# controleRemoto.net
KiCad netlist of a schematic drawn in Altium Designer
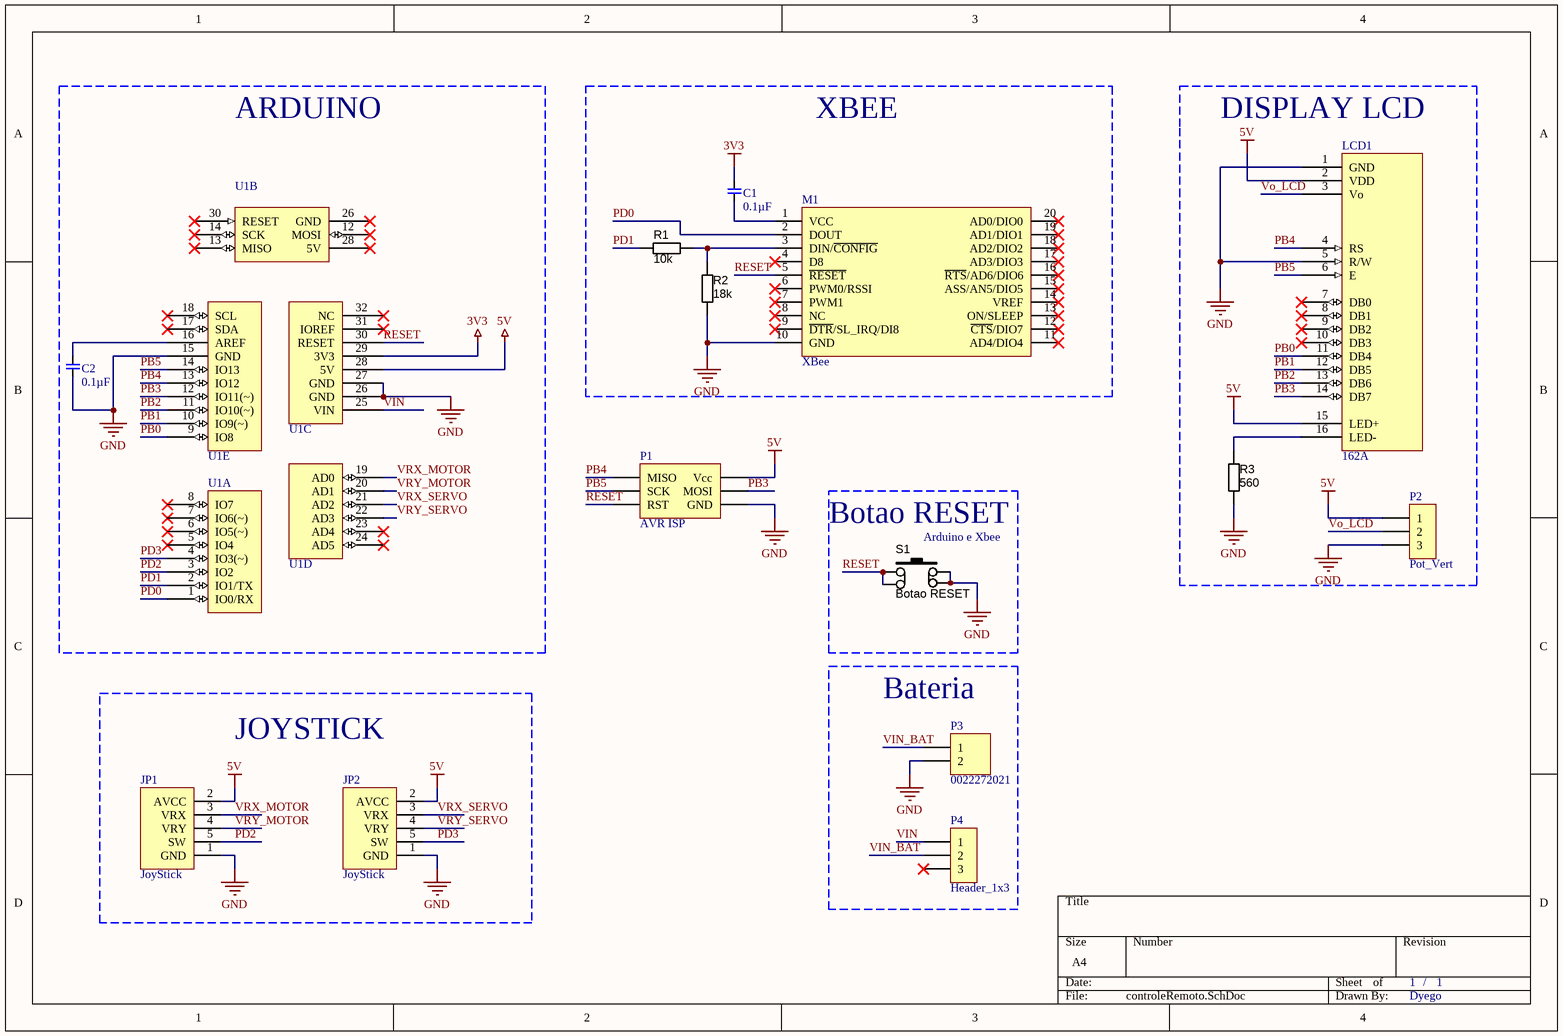
[diagram p0: controleRemoto.SchDoc]

(export (version "E")
  (design (tool "Eeschema 10.0.6"))
  (components
    (comp (ref "C1")
      (value "0.1µF")
      (footprint "C100-200-100")
      (description "Non-polarised capacitor")
      (fields
        (field (name "MANUFACTURER PART NUMBER") "C320C104K1R5TA7301")
        (field (name "TOLERANCE") "±10%")
      )
      (libsource (lib "DatabaseAltium") (part "Capacitor_non_polarized"))
    )
    (comp (ref "C2")
      (value "0.1µF")
      (footprint "C100-200-100")
      (description "Non-polarised capacitor")
      (fields
        (field (name "MANUFACTURER PART NUMBER") "C320C104K1R5TA7301")
        (field (name "TOLERANCE") "±10%")
      )
      (libsource (lib "DatabaseAltium") (part "Capacitor_non_polarized"))
    )
    (comp (ref "JP1")
      (value "JoyStick")
      (footprint "Modulo Joystick Dual Eixo XY")
      (libsource (lib "DatabaseAltium") (part "Joystick"))
    )
    (comp (ref "JP2")
      (value "JoyStick")
      (footprint "Modulo Joystick Dual Eixo XY")
      (libsource (lib "DatabaseAltium") (part "Joystick"))
    )
    (comp (ref "LCD1")
      (value "162A")
      (footprint "DISPLAY 16x2")
      (description "16 char * 2 line LCD character display with b/light")
      (fields (field (name "MANUFACTURERPARTNUMBER") "LCM-S01602DTR/A"))
      (libsource (lib "DatabaseAltium") (part "162A"))
    )
    (comp (ref "M1")
      (value "XBee")
      (footprint "XBee")
      (description "XBee RF Multipoint Module")
      (fields (field (name "MANUFACTURERPARTNUMBER") "XB24CZ7WIT-004"))
      (libsource (lib "DatabaseAltium") (part "XBee"))
    )
    (comp (ref "P1")
      (value "AVR ISP")
      (footprint "HDR-M-2x3-2.54mm-180-9.2mm")
      (description "ARV ISP Connector")
      (fields (field (name "MANUFACTURERPARTNUMBER") "AVR_ISP"))
      (libsource (lib "DatabaseAltium") (part "AVR_ISP"))
    )
    (comp (ref "P2")
      (value "Pot_Vert")
      (footprint "Pot_Vert")
      (description "Header, 1 Line, 3 Columns, 3 Pins")
      (libsource (lib "DatabaseAltium") (part "Pot_Vert"))
    )
    (comp (ref "P3")
      (value "0022272021")
      (footprint "KK_2")
      (libsource (lib "DatabaseAltium") (part "CONN_2"))
    )
    (comp (ref "P4")
      (value "Header_1x3")
      (footprint "Chave Alavanca MTS103")
      (description "Header, 1 Line, 3 Columns, 3 Pins")
      (fields (field (name "MANUFACTURERPARTNUMBER") "Chave alavanca"))
      (libsource (lib "DatabaseAltium") (part "Header_1x3"))
    )
    (comp (ref "R1")
      (value "10k")
      (footprint "RESTH_AXIAL-0.4")
      (description "Resistor")
      (fields (field (name "MANUFACTURER PART NUMBER") "CF18JT10K0") (field (name "TOLERANCE") "±5%"))
      (libsource (lib "DatabaseAltium") (part "Resistor"))
    )
    (comp (ref "R2")
      (value "18k")
      (footprint "RESTH_AXIAL-0.4")
      (description "Resistor")
      (fields (field (name "MANUFACTURER PART NUMBER") "CF18JT18K0") (field (name "TOLERANCE") "±5%"))
      (libsource (lib "") (part "Resistor_1"))
    )
    (comp (ref "R3")
      (value "560")
      (footprint "RESTH_AXIAL-0.4")
      (description "Resistor")
      (fields (field (name "MANUFACTURER PART NUMBER") "CF18JT560R") (field (name "TOLERANCE") "±5%"))
      (libsource (lib "") (part "Resistor_1"))
    )
    (comp (ref "S1")
      (value "Botao RESET")
      (footprint "DTS-6.0mm-6.0mm-THT")
      (fields (field (name "MANUFACTURERPARTNUMBER") "ADTS648NV"))
      (libsource (lib "DatabaseAltium") (part "PushButton"))
    )
    (comp (ref "U1")
      (value "Shield Arduino Uno Rv3 1")
      (footprint "Shield Arduino Uno Rv3 1")
      (libsource (lib "DatabaseAltium") (part "Arduino UNO Rev3"))
    )
  )
  (nets
    (net (code "1") (name "/PB0") (class "Default")
      (node (ref "LCD1") (pin "11") (pinfunction "DB4_11") (pintype "bidirectional"))
      (node (ref "U1") (pin "9") (pinfunction "IO8_9") (pintype "bidirectional"))
    )
    (net (code "2") (name "/PB1") (class "Default")
      (node (ref "LCD1") (pin "12") (pinfunction "DB5_12") (pintype "bidirectional"))
      (node (ref "U1") (pin "10") (pinfunction "IO9(~)_10") (pintype "bidirectional"))
    )
    (net (code "3") (name "/PB2") (class "Default")
      (node (ref "LCD1") (pin "13") (pinfunction "DB6_13") (pintype "bidirectional"))
      (node (ref "U1") (pin "11") (pinfunction "IO10(~)_11") (pintype "bidirectional"))
    )
    (net (code "4") (name "/PB3") (class "Default")
      (node (ref "LCD1") (pin "14") (pinfunction "DB7_14") (pintype "bidirectional"))
      (node (ref "P1") (pin "4") (pinfunction "MOSI_4") (pintype "passive"))
      (node (ref "U1") (pin "12") (pinfunction "IO11(~)_12") (pintype "bidirectional"))
    )
    (net (code "5") (name "/PB4") (class "Default")
      (node (ref "LCD1") (pin "4") (pinfunction "RS_4") (pintype "input"))
      (node (ref "P1") (pin "1") (pinfunction "MISO_1") (pintype "passive"))
      (node (ref "U1") (pin "13") (pinfunction "IO12_13") (pintype "bidirectional"))
    )
    (net (code "6") (name "/PB5") (class "Default")
      (node (ref "LCD1") (pin "6") (pinfunction "E_6") (pintype "input"))
      (node (ref "P1") (pin "3") (pinfunction "SCK_3") (pintype "passive"))
      (node (ref "U1") (pin "14") (pinfunction "IO13_14") (pintype "bidirectional"))
    )
    (net (code "7") (name "/PD0") (class "Default")
      (node (ref "M1") (pin "2") (pinfunction "DOUT_2") (pintype "passive"))
      (node (ref "U1") (pin "1") (pinfunction "IO0/RX_1") (pintype "bidirectional"))
    )
    (net (code "8") (name "/PD1") (class "Default")
      (node (ref "R1") (pin "1") (pinfunction "1_1") (pintype "passive"))
      (node (ref "U1") (pin "2") (pinfunction "IO1/TX_2") (pintype "bidirectional"))
    )
    (net (code "9") (name "/PD2") (class "Default")
      (node (ref "JP1") (pin "5") (pinfunction "SW_5") (pintype "passive"))
      (node (ref "U1") (pin "3") (pinfunction "IO2_3") (pintype "bidirectional"))
    )
    (net (code "10") (name "/PD3") (class "Default")
      (node (ref "JP2") (pin "5") (pinfunction "SW_5") (pintype "passive"))
      (node (ref "U1") (pin "4") (pinfunction "IO3(~)_4") (pintype "bidirectional"))
    )
    (net (code "11") (name "/RESET") (class "Default")
      (node (ref "M1") (pin "5") (pinfunction "~{RESET}_5") (pintype "passive"))
      (node (ref "P1") (pin "5") (pinfunction "RST_5") (pintype "passive"))
      (node (ref "S1") (pin "1") (pintype "passive"))
      (node (ref "U1") (pin "30") (pinfunction "RESET_30") (pintype "passive"))
    )
    (net (code "12") (name "/VIN") (class "Default")
      (node (ref "P4") (pin "1") (pinfunction "1_1") (pintype "passive"))
      (node (ref "U1") (pin "25") (pinfunction "VIN_25") (pintype "power_in"))
    )
    (net (code "13") (name "/VIN_BAT") (class "Default")
      (node (ref "P3") (pin "1") (pinfunction "1_1") (pintype "passive"))
      (node (ref "P4") (pin "2") (pinfunction "2_2") (pintype "passive"))
    )
    (net (code "14") (name "/VRX_MOTOR") (class "Default")
      (node (ref "JP1") (pin "3") (pinfunction "VRX_3") (pintype "passive"))
      (node (ref "U1") (pin "19") (pinfunction "AD0_19") (pintype "bidirectional"))
    )
    (net (code "15") (name "/VRX_SERVO") (class "Default")
      (node (ref "JP2") (pin "3") (pinfunction "VRX_3") (pintype "passive"))
      (node (ref "U1") (pin "21") (pinfunction "AD2_21") (pintype "bidirectional"))
    )
    (net (code "16") (name "/VRY_MOTOR") (class "Default")
      (node (ref "JP1") (pin "4") (pinfunction "VRY_4") (pintype "passive"))
      (node (ref "U1") (pin "20") (pinfunction "AD1_20") (pintype "bidirectional"))
    )
    (net (code "17") (name "/VRY_SERVO") (class "Default")
      (node (ref "JP2") (pin "4") (pinfunction "VRY_4") (pintype "passive"))
      (node (ref "U1") (pin "22") (pinfunction "AD3_22") (pintype "bidirectional"))
    )
    (net (code "18") (name "/Vo_LCD") (class "Default")
      (node (ref "LCD1") (pin "3") (pinfunction "Vo_3") (pintype "tri_state"))
      (node (ref "P2") (pin "2") (pinfunction "2_2") (pintype "passive"))
    )
    (net (code "19") (name "3V3") (class "Default")
      (node (ref "C1") (pin "2") (pinfunction "2_2") (pintype "passive"))
      (node (ref "U1") (pin "29") (pinfunction "3V3_29") (pintype "power_in"))
    )
    (net (code "20") (name "5V") (class "Default")
      (node (ref "JP1") (pin "2") (pinfunction "AVCC_2") (pintype "passive"))
      (node (ref "JP2") (pin "2") (pinfunction "AVCC_2") (pintype "passive"))
      (node (ref "LCD1") (pin "15") (pinfunction "LED+_15") (pintype "power_in"))
      (node (ref "LCD1") (pin "2") (pinfunction "VDD_2") (pintype "power_in"))
      (node (ref "P1") (pin "2") (pinfunction "Vcc_2") (pintype "passive"))
      (node (ref "P2") (pin "1") (pinfunction "1_1") (pintype "passive"))
      (node (ref "U1") (pin "28") (pinfunction "5V_28") (pintype "power_in"))
    )
    (net (code "21") (name "GND") (class "Default")
      (node (ref "C2") (pin "1") (pinfunction "1_1") (pintype "passive"))
      (node (ref "JP1") (pin "1") (pinfunction "GND_1") (pintype "passive"))
      (node (ref "JP2") (pin "1") (pinfunction "GND_1") (pintype "passive"))
      (node (ref "LCD1") (pin "1") (pinfunction "GND_1") (pintype "power_in"))
      (node (ref "LCD1") (pin "5") (pinfunction "R/W_5") (pintype "input"))
      (node (ref "M1") (pin "10") (pinfunction "GND_10") (pintype "passive"))
      (node (ref "P1") (pin "6") (pinfunction "GND_6") (pintype "passive"))
      (node (ref "P2") (pin "3") (pinfunction "3_3") (pintype "passive"))
      (node (ref "P3") (pin "2") (pinfunction "2_2") (pintype "passive"))
      (node (ref "R2") (pin "2") (pinfunction "2_2") (pintype "passive"))
      (node (ref "R3") (pin "2") (pinfunction "2_2") (pintype "passive"))
      (node (ref "S1") (pin "2") (pintype "passive"))
      (node (ref "U1") (pin "15") (pinfunction "GND_15") (pintype "power_in"))
      (node (ref "U1") (pin "26") (pinfunction "GND_26") (pintype "power_in"))
      (node (ref "U1") (pin "27") (pinfunction "GND_27") (pintype "power_in"))
    )
    (net (code "22") (name "Net-(LCD1-LED-)") (class "Default")
      (node (ref "LCD1") (pin "16") (pinfunction "LED-_16") (pintype "power_in"))
      (node (ref "R3") (pin "1") (pinfunction "1_1") (pintype "passive"))
    )
    (net (code "23") (name "Net-(M1-DIN{slash}~{CONFIG})") (class "Default")
      (node (ref "M1") (pin "3") (pinfunction "DIN/~{CONFIG}_3") (pintype "passive"))
      (node (ref "R1") (pin "2") (pinfunction "2_2") (pintype "passive"))
      (node (ref "R2") (pin "1") (pinfunction "1_1") (pintype "passive"))
    )
    (net (code "24") (name "Net-(M1-VCC)") (class "Default")
      (node (ref "C1") (pin "1") (pinfunction "1_1") (pintype "passive"))
      (node (ref "M1") (pin "1") (pinfunction "VCC_1") (pintype "passive"))
    )
    (net (code "25") (name "Net-(U1E-AREF)") (class "Default")
      (node (ref "C2") (pin "2") (pinfunction "2_2") (pintype "passive"))
      (node (ref "U1") (pin "16") (pinfunction "AREF_16") (pintype "passive"))
    )
    (net (code "26") (name "unconnected-(LCD1-DB0-Pad7)") (class "Default")
      (node (ref "LCD1") (pin "7") (pinfunction "DB0_7") (pintype "bidirectional+no_connect"))
    )
    (net (code "27") (name "unconnected-(LCD1-DB1-Pad8)") (class "Default")
      (node (ref "LCD1") (pin "8") (pinfunction "DB1_8") (pintype "bidirectional+no_connect"))
    )
    (net (code "28") (name "unconnected-(LCD1-DB2-Pad9)") (class "Default")
      (node (ref "LCD1") (pin "9") (pinfunction "DB2_9") (pintype "bidirectional+no_connect"))
    )
    (net (code "29") (name "unconnected-(LCD1-DB3-Pad10)") (class "Default")
      (node (ref "LCD1") (pin "10") (pinfunction "DB3_10") (pintype "bidirectional+no_connect"))
    )
    (net (code "30") (name "unconnected-(M1-AD0{slash}DIO0-Pad20)") (class "Default")
      (node (ref "M1") (pin "20") (pinfunction "AD0/DIO0_20") (pintype "passive+no_connect"))
    )
    (net (code "31") (name "unconnected-(M1-AD1{slash}DIO1-Pad19)") (class "Default")
      (node (ref "M1") (pin "19") (pinfunction "AD1/DIO1_19") (pintype "passive+no_connect"))
    )
    (net (code "32") (name "unconnected-(M1-AD2{slash}DIO2-Pad18)") (class "Default")
      (node (ref "M1") (pin "18") (pinfunction "AD2/DIO2_18") (pintype "passive+no_connect"))
    )
    (net (code "33") (name "unconnected-(M1-AD3{slash}DIO3-Pad17)") (class "Default")
      (node (ref "M1") (pin "17") (pinfunction "AD3/DIO3_17") (pintype "passive+no_connect"))
    )
    (net (code "34") (name "unconnected-(M1-AD4{slash}DIO4-Pad11)") (class "Default")
      (node (ref "M1") (pin "11") (pinfunction "AD4/DIO4_11") (pintype "passive+no_connect"))
    )
    (net (code "35") (name "unconnected-(M1-ASS{slash}AN5{slash}DIO5-Pad15)") (class "Default")
      (node (ref "M1") (pin "15") (pinfunction "ASS/AN5/DIO5_15") (pintype "passive+no_connect"))
    )
    (net (code "36") (name "unconnected-(M1-D8-Pad4)") (class "Default")
      (node (ref "M1") (pin "4") (pinfunction "D8_4") (pintype "passive+no_connect"))
    )
    (net (code "37") (name "unconnected-(M1-NC-Pad8)") (class "Default")
      (node (ref "M1") (pin "8") (pinfunction "NC_8") (pintype "passive+no_connect"))
    )
    (net (code "38") (name "unconnected-(M1-ON{slash}SLEEP-Pad13)") (class "Default")
      (node (ref "M1") (pin "13") (pinfunction "ON/SLEEP_13") (pintype "passive+no_connect"))
    )
    (net (code "39") (name "unconnected-(M1-PWM0{slash}RSSI-Pad6)") (class "Default")
      (node (ref "M1") (pin "6") (pinfunction "PWM0/RSSI_6") (pintype "passive+no_connect"))
    )
    (net (code "40") (name "unconnected-(M1-PWM1-Pad7)") (class "Default")
      (node (ref "M1") (pin "7") (pinfunction "PWM1_7") (pintype "passive+no_connect"))
    )
    (net (code "41") (name "unconnected-(M1-VREF-Pad14)") (class "Default")
      (node (ref "M1") (pin "14") (pinfunction "VREF_14") (pintype "passive+no_connect"))
    )
    (net (code "42") (name "unconnected-(M1-~{CTS}{slash}DIO7-Pad12)") (class "Default")
      (node (ref "M1") (pin "12") (pinfunction "~{CTS}/DIO7_12") (pintype "passive+no_connect"))
    )
    (net (code "43") (name "unconnected-(M1-~{DTR}{slash}SL_IRQ{slash}DI8-Pad9)") (class "Default")
      (node (ref "M1") (pin "9") (pinfunction "~{DTR}/SL_IRQ/DI8_9") (pintype "passive+no_connect"))
    )
    (net (code "44") (name "unconnected-(M1-~{RTS}{slash}AD6{slash}DIO6-Pad16)") (class "Default")
      (node (ref "M1") (pin "16") (pinfunction "~{RTS}/AD6/DIO6_16") (pintype "passive+no_connect"))
    )
    (net (code "45") (name "unconnected-(P4-Pad3)") (class "Default")
      (node (ref "P4") (pin "3") (pinfunction "3_3") (pintype "passive+no_connect"))
    )
    (net (code "46") (name "unconnected-(U1A-IO4-Pad5)") (class "Default")
      (node (ref "U1") (pin "5") (pinfunction "IO4_5") (pintype "bidirectional+no_connect"))
    )
    (net (code "47") (name "unconnected-(U1A-IO5(~)-Pad6)") (class "Default")
      (node (ref "U1") (pin "6") (pinfunction "IO5(~)_6") (pintype "bidirectional+no_connect"))
    )
    (net (code "48") (name "unconnected-(U1A-IO6(~)-Pad7)") (class "Default")
      (node (ref "U1") (pin "7") (pinfunction "IO6(~)_7") (pintype "bidirectional+no_connect"))
    )
    (net (code "49") (name "unconnected-(U1A-IO7-Pad8)") (class "Default")
      (node (ref "U1") (pin "8") (pinfunction "IO7_8") (pintype "bidirectional+no_connect"))
    )
    (net (code "50") (name "unconnected-(U1B-5V-Pad28)") (class "Default")
      (node (ref "U1") (pin "28") (pinfunction "5V_28") (pintype "power_in+no_connect"))
    )
    (net (code "51") (name "unconnected-(U1B-GND-Pad26)") (class "Default")
      (node (ref "U1") (pin "26") (pinfunction "GND_26") (pintype "power_in+no_connect"))
    )
    (net (code "52") (name "unconnected-(U1B-MISO-Pad13)") (class "Default")
      (node (ref "U1") (pin "13") (pinfunction "MISO_13") (pintype "bidirectional+no_connect"))
    )
    (net (code "53") (name "unconnected-(U1B-MOSI-Pad12)") (class "Default")
      (node (ref "U1") (pin "12") (pinfunction "MOSI_12") (pintype "bidirectional+no_connect"))
    )
    (net (code "54") (name "unconnected-(U1B-RESET-Pad30)") (class "Default")
      (node (ref "U1") (pin "30") (pinfunction "RESET_30") (pintype "input+no_connect"))
    )
    (net (code "55") (name "unconnected-(U1B-SCK-Pad14)") (class "Default")
      (node (ref "U1") (pin "14") (pinfunction "SCK_14") (pintype "bidirectional+no_connect"))
    )
    (net (code "56") (name "unconnected-(U1C-IOREF-Pad31)") (class "Default")
      (node (ref "U1") (pin "31") (pinfunction "IOREF_31") (pintype "power_in+no_connect"))
    )
    (net (code "57") (name "unconnected-(U1C-NC-Pad32)") (class "Default")
      (node (ref "U1") (pin "32") (pinfunction "NC_32") (pintype "passive+no_connect"))
    )
    (net (code "58") (name "unconnected-(U1D-AD4-Pad23)") (class "Default")
      (node (ref "U1") (pin "23") (pinfunction "AD4_23") (pintype "bidirectional+no_connect"))
    )
    (net (code "59") (name "unconnected-(U1D-AD5-Pad24)") (class "Default")
      (node (ref "U1") (pin "24") (pinfunction "AD5_24") (pintype "bidirectional+no_connect"))
    )
    (net (code "60") (name "unconnected-(U1E-SCL-Pad18)") (class "Default")
      (node (ref "U1") (pin "18") (pinfunction "SCL_18") (pintype "bidirectional+no_connect"))
    )
    (net (code "61") (name "unconnected-(U1E-SDA-Pad17)") (class "Default")
      (node (ref "U1") (pin "17") (pinfunction "SDA_17") (pintype "bidirectional+no_connect"))
    )
  )
)
